# mcu.net
KiCad netlist of a schematic drawn in Altium Designer
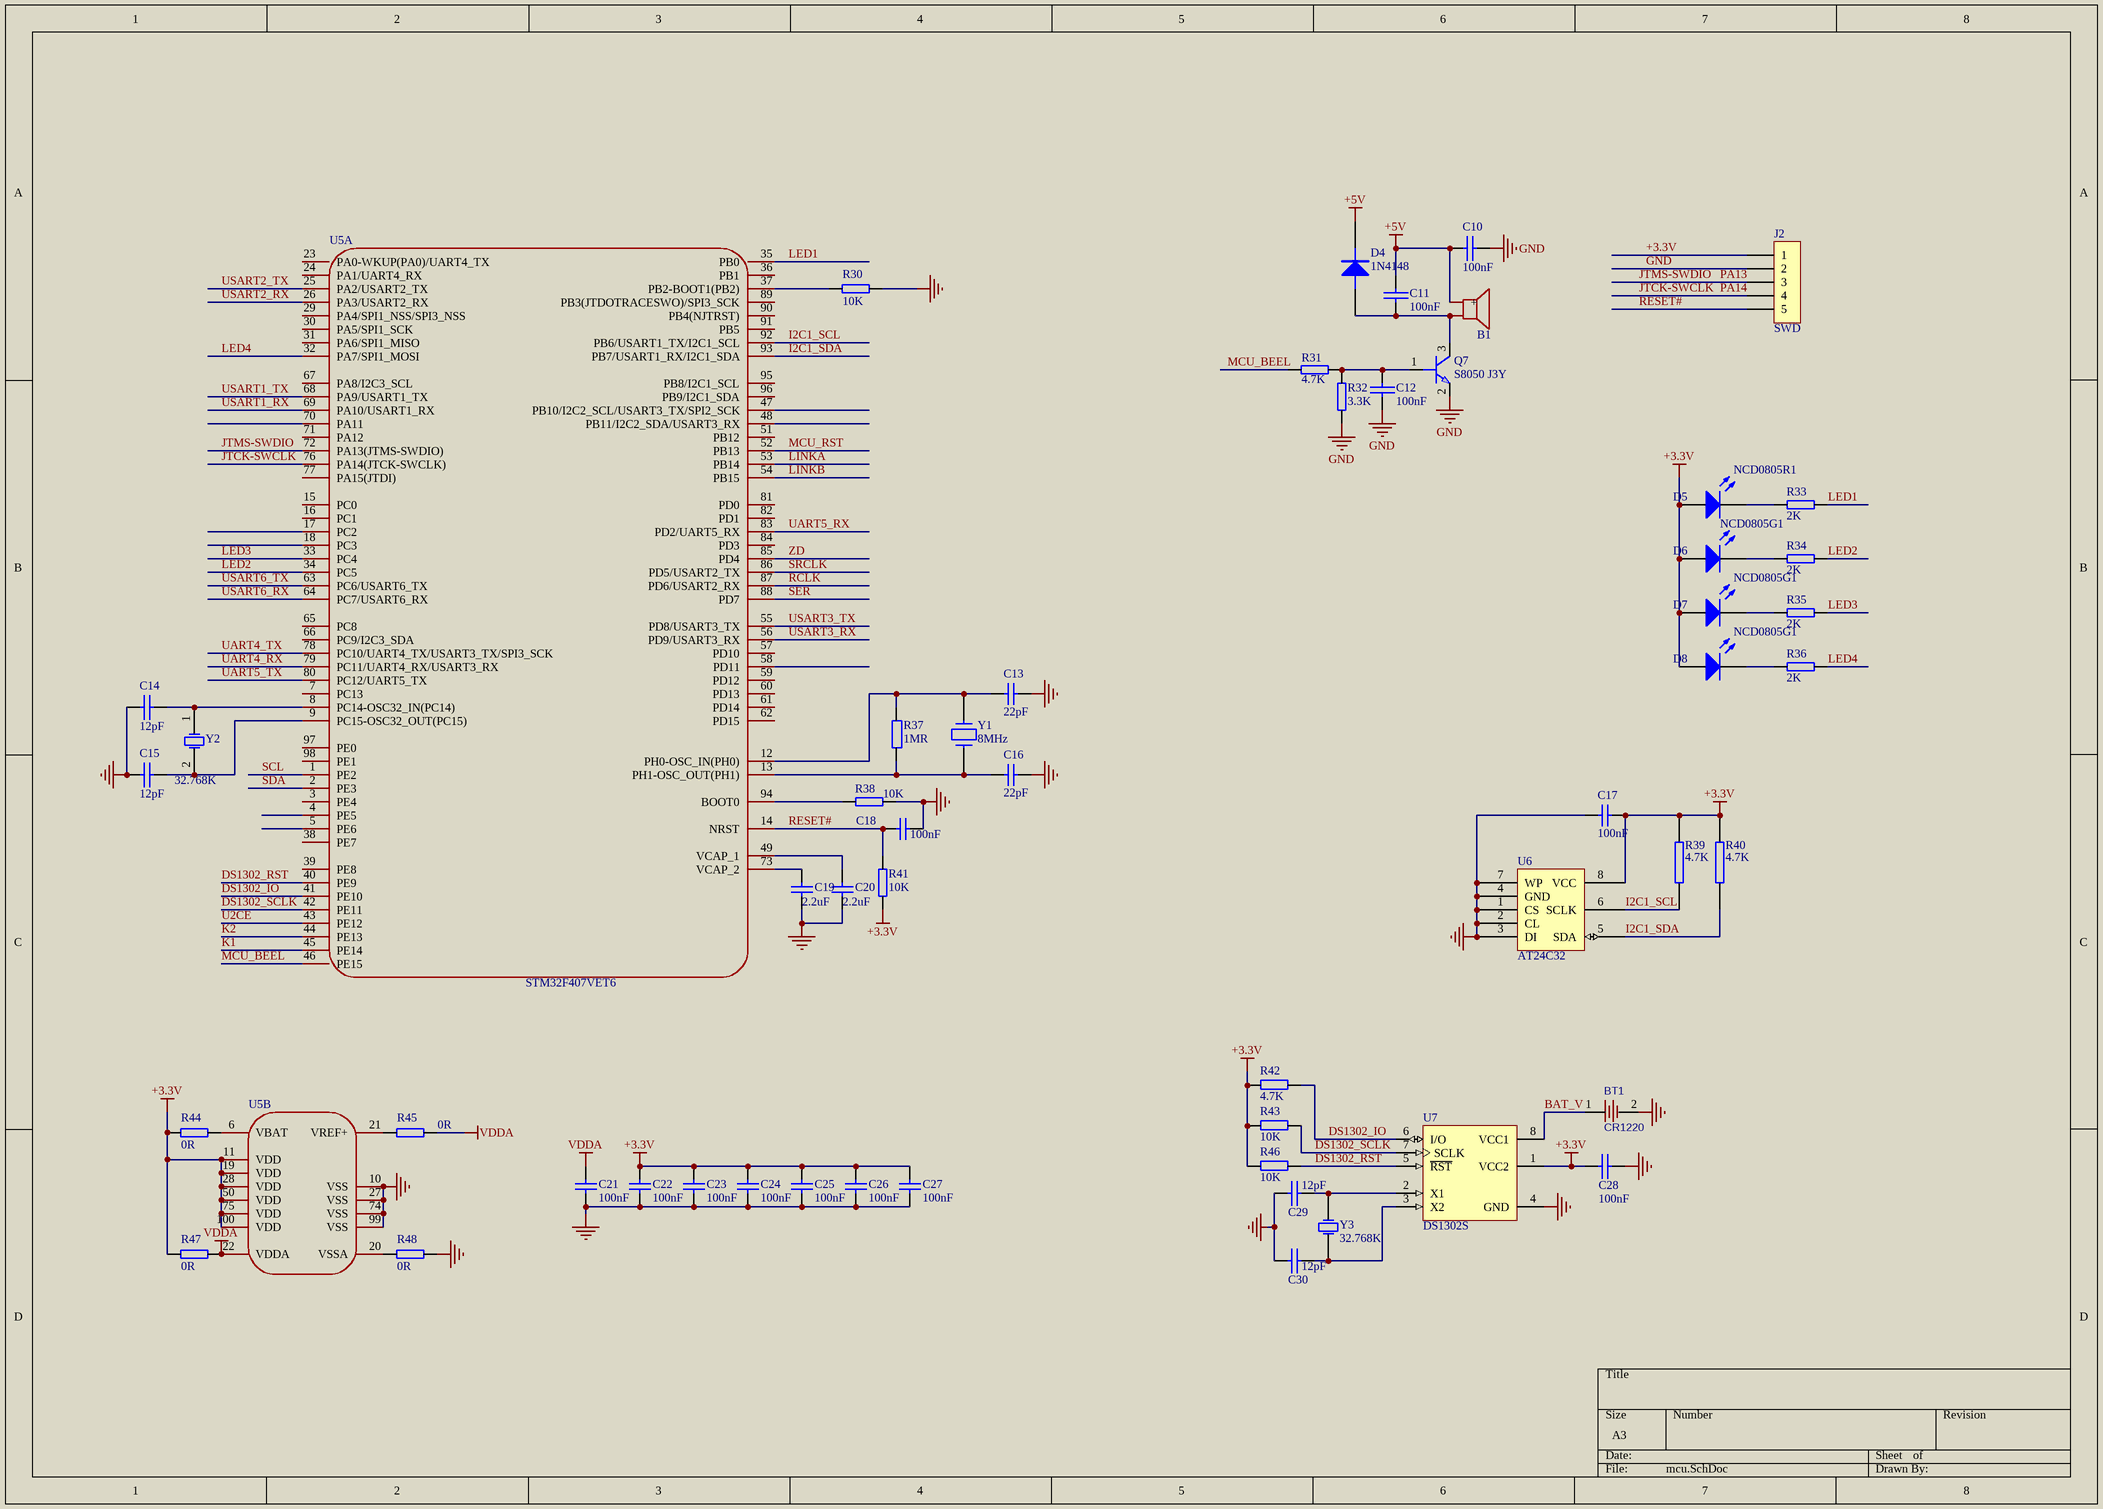
[diagram p0: mcu.SchDoc]

(export (version "E")
  (design (tool "Eeschema 10.0.6"))
  (components
    (comp (ref "B1")
      (value "2.4kHz")
      (footprint "BUZ-TH_BD12.0-P7.60-D0.6-FD")
      (fields (field (name "MANUFACTURER") "华能") (field (name "MANUFACTURER PART") "TMB12A05"))
      (libsource (lib "altium-import") (part "root_0_TMB12A05_C96093_"))
    )
    (comp (ref "BT1")
      (value "CR1220")
      (footprint "BAT-SMD_CR1220-2")
      (fields
        (field (name "BOM_SUPPLIER PART") "C238068")
        (field (name "BOM_MANUFACTURER PART") "1056TR")
        (field (name "CONTRIBUTOR") "LCSC")
      )
      (libsource (lib "altium-import") (part "root_0_1056TR_"))
    )
    (comp (ref "C10")
      (value "100nF")
      (footprint "LC-0805_C")
      (description "Capacitor")
      (libsource (lib "") (part "CAP_1"))
    )
    (comp (ref "C11")
      (value "100nF")
      (footprint "LC-0805_C")
      (description "Capacitor")
      (libsource (lib "") (part "CAP_1"))
    )
    (comp (ref "C12")
      (value "100nF")
      (footprint "LC-0805_C")
      (description "Capacitor")
      (libsource (lib "") (part "CAP_1"))
    )
    (comp (ref "C13")
      (value "22pF")
      (footprint "LC-0805_C")
      (description "Capacitor")
      (fields (field (name "PUBLISHER") "Altium Limited"))
      (libsource (lib "*") (part "CAP"))
    )
    (comp (ref "C14")
      (value "12pF")
      (footprint "LC-0805_C")
      (description "Capacitor")
      (libsource (lib "*") (part "普通电容"))
    )
    (comp (ref "C15")
      (value "12pF")
      (footprint "LC-0805_C")
      (description "Capacitor")
      (libsource (lib "*") (part "普通电容"))
    )
    (comp (ref "C16")
      (value "22pF")
      (footprint "LC-0805_C")
      (description "Capacitor")
      (fields (field (name "PUBLISHER") "Altium Limited"))
      (libsource (lib "*") (part "CAP"))
    )
    (comp (ref "C17")
      (value "100nF")
      (footprint "LC-0805_C")
      (description "Capacitor")
      (fields (field (name "PUBLISHER") "Altium Limited"))
      (libsource (lib "*") (part "CAP"))
    )
    (comp (ref "C18")
      (value "100nF")
      (footprint "LC-0805_C")
      (description "Capacitor")
      (fields (field (name "PUBLISHER") "Altium Limited"))
      (libsource (lib "*") (part "CAP"))
    )
    (comp (ref "C19")
      (value "2.2uF")
      (footprint "LC-0805_C")
      (description "Capacitor")
      (fields (field (name "PUBLISHER") "Altium Limited"))
      (libsource (lib "*") (part "CAP"))
    )
    (comp (ref "C20")
      (value "2.2uF")
      (footprint "LC-0805_C")
      (description "Capacitor")
      (fields (field (name "PUBLISHER") "Altium Limited"))
      (libsource (lib "*") (part "CAP"))
    )
    (comp (ref "C21")
      (value "100nF")
      (footprint "LC-0805_C")
      (description "Capacitor")
      (fields (field (name "PUBLISHER") "Altium Limited"))
      (libsource (lib "*") (part "CAP"))
    )
    (comp (ref "C22")
      (value "100nF")
      (footprint "LC-0805_C")
      (description "Capacitor")
      (fields (field (name "PUBLISHER") "Altium Limited"))
      (libsource (lib "*") (part "CAP"))
    )
    (comp (ref "C23")
      (value "100nF")
      (footprint "LC-0805_C")
      (description "Capacitor")
      (fields (field (name "PUBLISHER") "Altium Limited"))
      (libsource (lib "*") (part "CAP"))
    )
    (comp (ref "C24")
      (value "100nF")
      (footprint "LC-0805_C")
      (description "Capacitor")
      (fields (field (name "PUBLISHER") "Altium Limited"))
      (libsource (lib "*") (part "CAP"))
    )
    (comp (ref "C25")
      (value "100nF")
      (footprint "LC-0805_C")
      (description "Capacitor")
      (fields (field (name "PUBLISHER") "Altium Limited"))
      (libsource (lib "*") (part "CAP"))
    )
    (comp (ref "C26")
      (value "100nF")
      (footprint "LC-0805_C")
      (description "Capacitor")
      (fields (field (name "PUBLISHER") "Altium Limited"))
      (libsource (lib "*") (part "CAP"))
    )
    (comp (ref "C27")
      (value "100nF")
      (footprint "LC-0805_C")
      (description "Capacitor")
      (fields (field (name "PUBLISHER") "Altium Limited"))
      (libsource (lib "*") (part "CAP"))
    )
    (comp (ref "C28")
      (value "100nF")
      (footprint "LC-0805_C")
      (description "Capacitor")
      (libsource (lib "*") (part "普通电容"))
    )
    (comp (ref "C29")
      (value "12pF")
      (footprint "LC-0805_C")
      (description "Capacitor")
      (libsource (lib "*") (part "普通电容"))
    )
    (comp (ref "C30")
      (value "12pF")
      (footprint "LC-0805_C")
      (description "Capacitor")
      (libsource (lib "*") (part "普通电容"))
    )
    (comp (ref "D4")
      (value "1N4148")
      (footprint "LC-SOD-123")
      (description "Diode")
      (libsource (lib "*") (part "DIODE"))
    )
    (comp (ref "D5")
      (value "NCD0805R1")
      (footprint "LC-0805_LED_S1")
      (description "Typical RED, GREEN, YELLOW, AMBER GaAs LED")
      (fields (field (name "PUBLISHER") "Altium Limited"))
      (libsource (lib "Miscellaneous Devices") (part "LED2"))
    )
    (comp (ref "D6")
      (value "NCD0805G1")
      (footprint "LC-0805_LED_S1")
      (description "Typical RED, GREEN, YELLOW, AMBER GaAs LED")
      (fields (field (name "PUBLISHER") "Altium Limited"))
      (libsource (lib "Miscellaneous Devices") (part "LED2"))
    )
    (comp (ref "D7")
      (value "NCD0805G1")
      (footprint "LC-0805_LED_S1")
      (description "Typical RED, GREEN, YELLOW, AMBER GaAs LED")
      (fields (field (name "PUBLISHER") "Altium Limited"))
      (libsource (lib "Miscellaneous Devices") (part "LED2"))
    )
    (comp (ref "D8")
      (value "NCD0805G1")
      (footprint "LC-0805_LED_S1")
      (description "Typical RED, GREEN, YELLOW, AMBER GaAs LED")
      (fields (field (name "PUBLISHER") "Altium Limited"))
      (libsource (lib "Miscellaneous Devices") (part "LED2"))
    )
    (comp (ref "J2")
      (value "SWD")
      (footprint "HDR1X5")
      (description "Connector")
      (libsource (lib "*") (part "CON5"))
    )
    (comp (ref "Q7") (value "S8050 J3Y") (footprint "SOT-23") (libsource (lib "*") (part "2N5551")))
    (comp (ref "R30")
      (value "10K")
      (footprint "LC-0805_R")
      (description "1K")
      (libsource (lib "*") (part "RES22"))
    )
    (comp (ref "R31")
      (value "4.7K")
      (footprint "LC-0805_R")
      (description "1K")
      (libsource (lib "*") (part "RES22"))
    )
    (comp (ref "R32")
      (value "3.3K")
      (footprint "LC-0805_R")
      (description "1K")
      (libsource (lib "*") (part "RES22"))
    )
    (comp (ref "R33")
      (value "2K")
      (footprint "LC-0805_R")
      (description "1K")
      (libsource (lib "*") (part "RES22"))
    )
    (comp (ref "R34")
      (value "2K")
      (footprint "LC-0805_R")
      (description "1K")
      (libsource (lib "*") (part "RES22"))
    )
    (comp (ref "R35")
      (value "2K")
      (footprint "LC-0805_R")
      (description "1K")
      (libsource (lib "*") (part "RES22"))
    )
    (comp (ref "R36")
      (value "2K")
      (footprint "LC-0805_R")
      (description "1K")
      (libsource (lib "*") (part "RES22"))
    )
    (comp (ref "R37") (value "1MR") (footprint "LC-0805_R") (libsource (lib "ATK-SIM900A") (part "R")))
    (comp (ref "R38")
      (value "10K")
      (footprint "LC-0805_R")
      (description "1K")
      (libsource (lib "*") (part "RES22"))
    )
    (comp (ref "R39") (value "4.7K") (footprint "LC-0805_R") (libsource (lib "*") (part "RES2")))
    (comp (ref "R40") (value "4.7K") (footprint "LC-0805_R") (libsource (lib "*") (part "RES2")))
    (comp (ref "R41")
      (value "10K")
      (footprint "LC-0805_R")
      (description "1K")
      (libsource (lib "*") (part "RES22"))
    )
    (comp (ref "R42") (value "4.7K") (footprint "LC-0805_R") (libsource (lib "ATK-SIM900A") (part "R")))
    (comp (ref "R43") (value "10K") (footprint "LC-0805_R") (libsource (lib "ATK-SIM900A") (part "R")))
    (comp (ref "R44")
      (value "0R")
      (footprint "LC-0805_R")
      (description "1K")
      (libsource (lib "*") (part "RES22"))
    )
    (comp (ref "R45")
      (value "0R")
      (footprint "LC-0805_R")
      (description "1K")
      (libsource (lib "*") (part "RES22"))
    )
    (comp (ref "R46") (value "10K") (footprint "LC-0805_R") (libsource (lib "ATK-SIM900A") (part "R")))
    (comp (ref "R47")
      (value "0R")
      (footprint "LC-0805_R")
      (description "1K")
      (libsource (lib "*") (part "RES22"))
    )
    (comp (ref "R48")
      (value "0R")
      (footprint "LC-0805_R")
      (description "1K")
      (libsource (lib "*") (part "RES22"))
    )
    (comp (ref "U5")
      (value "STM32F407VET6")
      (footprint "LC-LQFP-100_14x14x05P")
      (fields (field (name "MANUFACTURER") "ST(意法半导体)"))
      (libsource (lib "stm32f407ve") (part "STM32F407VET6"))
    )
    (comp (ref "U6") (value "AT24C32") (footprint "LC-SOIC-8_150mil") (libsource (lib "*") (part "24C64")))
    (comp (ref "U7")
      (value "DS1302S")
      (footprint "LC-SOIC-8_150mil")
      (description "Trickle Charge Timekeeping Chip")
      (fields (field (name "PUBLISHER") "Altium Limited"))
      (libsource (lib "Dallas Peripheral Real Time Clock") (part "DS1302S"))
    )
    (comp (ref "Y1")
      (value "8MHz")
      (footprint "XTALSO")
      (description "Crystal")
      (libsource (lib "*") (part "CRYSTAL"))
    )
    (comp (ref "Y2")
      (value "32.768K")
      (footprint "LC-SMD-3215_2P FC - 135")
      (description "Crystal Oscillator")
      (fields (field (name "PUBLISHER") "Altium Limited"))
      (libsource (lib "") (part "XTAL_1"))
    )
    (comp (ref "Y3")
      (value "32.768K")
      (footprint "LC-SMD-3215_2P FC - 135")
      (description "Crystal Oscillator")
      (fields (field (name "PUBLISHER") "Altium Limited"))
      (libsource (lib "*") (part "XTAL"))
    )
  )
  (nets
    (net (code "1") (name "+3.3V") (class "Default")
      (node (ref "C17") (pin "1") (pinfunction "1_1") (pintype "passive"))
      (node (ref "C22") (pin "2") (pinfunction "2_2") (pintype "passive"))
      (node (ref "C23") (pin "2") (pinfunction "2_2") (pintype "passive"))
      (node (ref "C24") (pin "2") (pinfunction "2_2") (pintype "passive"))
      (node (ref "C25") (pin "2") (pinfunction "2_2") (pintype "passive"))
      (node (ref "C26") (pin "2") (pinfunction "2_2") (pintype "passive"))
      (node (ref "C27") (pin "2") (pinfunction "2_2") (pintype "passive"))
      (node (ref "C28") (pin "1") (pinfunction "1_1") (pintype "passive"))
      (node (ref "D5") (pin "1") (pinfunction "A_1") (pintype "passive"))
      (node (ref "D6") (pin "1") (pinfunction "A_1") (pintype "passive"))
      (node (ref "D7") (pin "1") (pinfunction "A_1") (pintype "passive"))
      (node (ref "D8") (pin "1") (pinfunction "A_1") (pintype "passive"))
      (node (ref "J2") (pin "1") (pinfunction "1_1") (pintype "passive"))
      (node (ref "R39") (pin "2") (pinfunction "2_2") (pintype "passive"))
      (node (ref "R40") (pin "2") (pinfunction "2_2") (pintype "passive"))
      (node (ref "R41") (pin "1") (pintype "passive"))
      (node (ref "R42") (pin "2") (pintype "passive"))
      (node (ref "R43") (pin "2") (pintype "passive"))
      (node (ref "R44") (pin "1") (pintype "passive"))
      (node (ref "R46") (pin "2") (pintype "passive"))
      (node (ref "R47") (pin "1") (pintype "passive"))
      (node (ref "U5") (pin "100") (pinfunction "VDD_100") (pintype "passive"))
      (node (ref "U5") (pin "11") (pinfunction "VDD_11") (pintype "passive"))
      (node (ref "U5") (pin "19") (pinfunction "VDD_19") (pintype "passive"))
      (node (ref "U5") (pin "28") (pinfunction "VDD_28") (pintype "passive"))
      (node (ref "U5") (pin "50") (pinfunction "VDD_50") (pintype "passive"))
      (node (ref "U5") (pin "75") (pinfunction "VDD_75") (pintype "passive"))
      (node (ref "U6") (pin "8") (pinfunction "VCC_8") (pintype "power_in"))
      (node (ref "U7") (pin "1") (pinfunction "VCC2_1") (pintype "power_in"))
    )
    (net (code "2") (name "+5V") (class "Default")
      (node (ref "B1") (pin "1") (pinfunction "+_1") (pintype "passive"))
      (node (ref "C10") (pin "1") (pinfunction "1_1") (pintype "passive"))
      (node (ref "C11") (pin "1") (pinfunction "1_1") (pintype "passive"))
      (node (ref "D4") (pin "2") (pinfunction "K_2") (pintype "passive"))
    )
    (net (code "3") (name "/BAT_V") (class "Default")
      (node (ref "BT1") (pin "1") (pinfunction "1_1") (pintype "passive"))
      (node (ref "U7") (pin "8") (pinfunction "VCC1_8") (pintype "power_in"))
    )
    (net (code "4") (name "/DS1302_IO") (class "Default")
      (node (ref "R42") (pin "1") (pintype "passive"))
      (node (ref "U5") (pin "41") (pinfunction "PE10_41") (pintype "passive"))
      (node (ref "U7") (pin "6") (pinfunction "I/O_6") (pintype "bidirectional"))
    )
    (net (code "5") (name "/DS1302_RST") (class "Default")
      (node (ref "R46") (pin "1") (pintype "passive"))
      (node (ref "U5") (pin "40") (pinfunction "PE9_40") (pintype "passive"))
      (node (ref "U7") (pin "5") (pinfunction "~{RST}_5") (pintype "input"))
    )
    (net (code "6") (name "/DS1302_SCLK") (class "Default")
      (node (ref "R43") (pin "1") (pintype "passive"))
      (node (ref "U5") (pin "42") (pinfunction "PE11_42") (pintype "passive"))
      (node (ref "U7") (pin "7") (pinfunction "SCLK_7") (pintype "input"))
    )
    (net (code "7") (name "/I2C1_SCL") (class "Default")
      (node (ref "R39") (pin "1") (pinfunction "1_1") (pintype "passive"))
      (node (ref "U5") (pin "92") (pinfunction "PB6/USART1_TX/I2C1_SCL_92") (pintype "passive"))
      (node (ref "U6") (pin "6") (pinfunction "SCLK_6") (pintype "passive"))
    )
    (net (code "8") (name "/I2C1_SDA") (class "Default")
      (node (ref "R40") (pin "1") (pinfunction "1_1") (pintype "passive"))
      (node (ref "U5") (pin "93") (pinfunction "PB7/USART1_RX/I2C1_SDA_93") (pintype "passive"))
      (node (ref "U6") (pin "5") (pinfunction "SDA_5") (pintype "bidirectional"))
    )
    (net (code "9") (name "/JTCK-SWCLK") (class "Default")
      (node (ref "J2") (pin "4") (pinfunction "4_4") (pintype "passive"))
      (node (ref "U5") (pin "76") (pinfunction "PA14(JTCK-SWCLK)_76") (pintype "passive"))
    )
    (net (code "10") (name "/JTMS-SWDIO") (class "Default")
      (node (ref "J2") (pin "3") (pinfunction "3_3") (pintype "passive"))
      (node (ref "U5") (pin "72") (pinfunction "PA13(JTMS-SWDIO)_72") (pintype "passive"))
    )
    (net (code "11") (name "/K1") (class "Default")
      (node (ref "U5") (pin "45") (pinfunction "PE14_45") (pintype "passive"))
    )
    (net (code "12") (name "/K2") (class "Default")
      (node (ref "U5") (pin "44") (pinfunction "PE13_44") (pintype "passive"))
    )
    (net (code "13") (name "/LED1") (class "Default")
      (node (ref "R33") (pin "1") (pintype "passive"))
      (node (ref "U5") (pin "35") (pinfunction "PB0_35") (pintype "passive"))
    )
    (net (code "14") (name "/LED2") (class "Default")
      (node (ref "R34") (pin "1") (pintype "passive"))
      (node (ref "U5") (pin "34") (pinfunction "PC5_34") (pintype "passive"))
    )
    (net (code "15") (name "/LED3") (class "Default")
      (node (ref "R35") (pin "1") (pintype "passive"))
      (node (ref "U5") (pin "33") (pinfunction "PC4_33") (pintype "passive"))
    )
    (net (code "16") (name "/LED4") (class "Default")
      (node (ref "R36") (pin "1") (pintype "passive"))
      (node (ref "U5") (pin "32") (pinfunction "PA7/SPI1_MOSI_32") (pintype "passive"))
    )
    (net (code "17") (name "/LINKA") (class "Default")
      (node (ref "U5") (pin "53") (pinfunction "PB14_53") (pintype "passive"))
    )
    (net (code "18") (name "/LINKB") (class "Default")
      (node (ref "U5") (pin "54") (pinfunction "PB15_54") (pintype "passive"))
    )
    (net (code "19") (name "/MCU_BEEL") (class "Default")
      (node (ref "R31") (pin "1") (pintype "passive"))
      (node (ref "U5") (pin "46") (pinfunction "PE15_46") (pintype "passive"))
    )
    (net (code "20") (name "/MCU_RST") (class "Default")
      (node (ref "U5") (pin "52") (pinfunction "PB13_52") (pintype "passive"))
    )
    (net (code "21") (name "/RCLK") (class "Default")
      (node (ref "U5") (pin "87") (pinfunction "PD6/USART2_RX_87") (pintype "passive"))
    )
    (net (code "22") (name "/RESET#") (class "Default")
      (node (ref "C18") (pin "1") (pinfunction "1_1") (pintype "passive"))
      (node (ref "J2") (pin "5") (pinfunction "5_5") (pintype "passive"))
      (node (ref "R41") (pin "2") (pintype "passive"))
      (node (ref "U5") (pin "14") (pinfunction "NRST_14") (pintype "passive"))
    )
    (net (code "23") (name "/SCL") (class "Default")
      (node (ref "U5") (pin "1") (pinfunction "PE2_1") (pintype "passive"))
    )
    (net (code "24") (name "/SDA") (class "Default")
      (node (ref "U5") (pin "2") (pinfunction "PE3_2") (pintype "passive"))
    )
    (net (code "25") (name "/SER") (class "Default")
      (node (ref "U5") (pin "88") (pinfunction "PD7_88") (pintype "passive"))
    )
    (net (code "26") (name "/SRCLK") (class "Default")
      (node (ref "U5") (pin "86") (pinfunction "PD5/USART2_TX_86") (pintype "passive"))
    )
    (net (code "27") (name "/U2CE") (class "Default")
      (node (ref "U5") (pin "43") (pinfunction "PE12_43") (pintype "passive"))
    )
    (net (code "28") (name "/UART4_RX") (class "Default")
      (node (ref "U5") (pin "79") (pinfunction "PC11/UART4_RX/USART3_RX_79") (pintype "passive"))
    )
    (net (code "29") (name "/UART4_TX") (class "Default")
      (node (ref "U5") (pin "78") (pinfunction "PC10/UART4_TX/USART3_TX/SPI3_SCK_78") (pintype "passive"))
    )
    (net (code "30") (name "/UART5_RX") (class "Default")
      (node (ref "U5") (pin "83") (pinfunction "PD2/UART5_RX_83") (pintype "passive"))
    )
    (net (code "31") (name "/UART5_TX") (class "Default")
      (node (ref "U5") (pin "80") (pinfunction "PC12/UART5_TX_80") (pintype "passive"))
    )
    (net (code "32") (name "/USART1_RX") (class "Default")
      (node (ref "U5") (pin "69") (pinfunction "PA10/USART1_RX_69") (pintype "passive"))
    )
    (net (code "33") (name "/USART1_TX") (class "Default")
      (node (ref "U5") (pin "68") (pinfunction "PA9/USART1_TX_68") (pintype "passive"))
    )
    (net (code "34") (name "/USART2_RX") (class "Default")
      (node (ref "U5") (pin "26") (pinfunction "PA3/USART2_RX_26") (pintype "passive"))
    )
    (net (code "35") (name "/USART2_TX") (class "Default")
      (node (ref "U5") (pin "25") (pinfunction "PA2/USART2_TX_25") (pintype "passive"))
    )
    (net (code "36") (name "/USART3_RX") (class "Default")
      (node (ref "U5") (pin "56") (pinfunction "PD9/USART3_RX_56") (pintype "passive"))
    )
    (net (code "37") (name "/USART3_TX") (class "Default")
      (node (ref "U5") (pin "55") (pinfunction "PD8/USART3_TX_55") (pintype "passive"))
    )
    (net (code "38") (name "/USART6_RX") (class "Default")
      (node (ref "U5") (pin "64") (pinfunction "PC7/USART6_RX_64") (pintype "passive"))
    )
    (net (code "39") (name "/USART6_TX") (class "Default")
      (node (ref "U5") (pin "63") (pinfunction "PC6/USART6_TX_63") (pintype "passive"))
    )
    (net (code "40") (name "/ZD") (class "Default")
      (node (ref "U5") (pin "85") (pinfunction "PD4_85") (pintype "passive"))
    )
    (net (code "41") (name "GND") (class "Default")
      (node (ref "BT1") (pin "2") (pinfunction "2_2") (pintype "passive"))
      (node (ref "C10") (pin "2") (pinfunction "2_2") (pintype "passive"))
      (node (ref "C12") (pin "2") (pinfunction "2_2") (pintype "passive"))
      (node (ref "C13") (pin "1") (pinfunction "1_1") (pintype "passive"))
      (node (ref "C14") (pin "1") (pinfunction "1_1") (pintype "passive"))
      (node (ref "C15") (pin "1") (pinfunction "1_1") (pintype "passive"))
      (node (ref "C16") (pin "2") (pinfunction "2_2") (pintype "passive"))
      (node (ref "C17") (pin "2") (pinfunction "2_2") (pintype "passive"))
      (node (ref "C18") (pin "2") (pinfunction "2_2") (pintype "passive"))
      (node (ref "C19") (pin "1") (pinfunction "1_1") (pintype "passive"))
      (node (ref "C20") (pin "1") (pinfunction "1_1") (pintype "passive"))
      (node (ref "C21") (pin "1") (pinfunction "1_1") (pintype "passive"))
      (node (ref "C22") (pin "1") (pinfunction "1_1") (pintype "passive"))
      (node (ref "C23") (pin "1") (pinfunction "1_1") (pintype "passive"))
      (node (ref "C24") (pin "1") (pinfunction "1_1") (pintype "passive"))
      (node (ref "C25") (pin "1") (pinfunction "1_1") (pintype "passive"))
      (node (ref "C26") (pin "1") (pinfunction "1_1") (pintype "passive"))
      (node (ref "C27") (pin "1") (pinfunction "1_1") (pintype "passive"))
      (node (ref "C28") (pin "2") (pinfunction "2_2") (pintype "passive"))
      (node (ref "C29") (pin "1") (pinfunction "1_1") (pintype "passive"))
      (node (ref "C30") (pin "1") (pinfunction "1_1") (pintype "passive"))
      (node (ref "J2") (pin "2") (pinfunction "2_2") (pintype "passive"))
      (node (ref "Q7") (pin "2") (pinfunction "E_2") (pintype "passive"))
      (node (ref "R30") (pin "2") (pintype "passive"))
      (node (ref "R32") (pin "1") (pintype "passive"))
      (node (ref "R38") (pin "2") (pintype "passive"))
      (node (ref "R48") (pin "2") (pintype "passive"))
      (node (ref "U5") (pin "10") (pinfunction "VSS_10") (pintype "passive"))
      (node (ref "U5") (pin "27") (pinfunction "VSS_27") (pintype "passive"))
      (node (ref "U5") (pin "74") (pinfunction "VSS_74") (pintype "passive"))
      (node (ref "U5") (pin "99") (pinfunction "VSS_99") (pintype "passive"))
      (node (ref "U6") (pin "1") (pinfunction "CS_1") (pintype "passive"))
      (node (ref "U6") (pin "2") (pinfunction "CL_2") (pintype "passive"))
      (node (ref "U6") (pin "3") (pinfunction "DI_3") (pintype "passive"))
      (node (ref "U6") (pin "4") (pinfunction "GND_4") (pintype "power_in"))
      (node (ref "U6") (pin "7") (pinfunction "WP_7") (pintype "passive"))
      (node (ref "U7") (pin "4") (pinfunction "GND_4") (pintype "power_in"))
    )
    (net (code "42") (name "Net-(D4-A)") (class "Default")
      (node (ref "B1") (pin "2") (pinfunction "2_2") (pintype "passive"))
      (node (ref "C11") (pin "2") (pinfunction "2_2") (pintype "passive"))
      (node (ref "D4") (pin "1") (pinfunction "A_1") (pintype "passive"))
      (node (ref "Q7") (pin "3") (pinfunction "C_3") (pintype "passive"))
    )
    (net (code "43") (name "Net-(D5-K)") (class "Default")
      (node (ref "D5") (pin "2") (pinfunction "K_2") (pintype "passive"))
      (node (ref "R33") (pin "2") (pintype "passive"))
    )
    (net (code "44") (name "Net-(D6-K)") (class "Default")
      (node (ref "D6") (pin "2") (pinfunction "K_2") (pintype "passive"))
      (node (ref "R34") (pin "2") (pintype "passive"))
    )
    (net (code "45") (name "Net-(D7-K)") (class "Default")
      (node (ref "D7") (pin "2") (pinfunction "K_2") (pintype "passive"))
      (node (ref "R35") (pin "2") (pintype "passive"))
    )
    (net (code "46") (name "Net-(D8-K)") (class "Default")
      (node (ref "D8") (pin "2") (pinfunction "K_2") (pintype "passive"))
      (node (ref "R36") (pin "2") (pintype "passive"))
    )
    (net (code "47") (name "Net-(Q7-B)") (class "Default")
      (node (ref "C12") (pin "1") (pinfunction "1_1") (pintype "passive"))
      (node (ref "Q7") (pin "1") (pinfunction "B_1") (pintype "passive"))
      (node (ref "R31") (pin "2") (pintype "passive"))
      (node (ref "R32") (pin "2") (pintype "passive"))
    )
    (net (code "48") (name "Net-(U5A-BOOT0)") (class "Default")
      (node (ref "R38") (pin "1") (pintype "passive"))
      (node (ref "U5") (pin "94") (pinfunction "BOOT0_94") (pintype "passive"))
    )
    (net (code "49") (name "Net-(U5A-PB2-BOOT1(PB2))") (class "Default")
      (node (ref "R30") (pin "1") (pintype "passive"))
      (node (ref "U5") (pin "37") (pinfunction "PB2-BOOT1(PB2)_37") (pintype "passive"))
    )
    (net (code "50") (name "Net-(U5A-PC14-OSC32_IN(PC14))") (class "Default")
      (node (ref "C14") (pin "2") (pinfunction "2_2") (pintype "passive"))
      (node (ref "U5") (pin "8") (pinfunction "PC14-OSC32_IN(PC14)_8") (pintype "passive"))
      (node (ref "Y2") (pin "1") (pinfunction "OSC1_1") (pintype "passive"))
    )
    (net (code "51") (name "Net-(U5A-PC15-OSC32_OUT(PC15))") (class "Default")
      (node (ref "C15") (pin "2") (pinfunction "2_2") (pintype "passive"))
      (node (ref "U5") (pin "9") (pinfunction "PC15-OSC32_OUT(PC15)_9") (pintype "passive"))
      (node (ref "Y2") (pin "2") (pinfunction "OSC2_2") (pintype "passive"))
    )
    (net (code "52") (name "Net-(U5A-PH0-OSC_IN(PH0))") (class "Default")
      (node (ref "C13") (pin "2") (pinfunction "2_2") (pintype "passive"))
      (node (ref "R37") (pin "2") (pintype "passive"))
      (node (ref "U5") (pin "12") (pinfunction "PH0-OSC_IN(PH0)_12") (pintype "passive"))
      (node (ref "Y1") (pin "1") (pinfunction "1_1") (pintype "passive"))
    )
    (net (code "53") (name "Net-(U5A-PH1-OSC_OUT(PH1))") (class "Default")
      (node (ref "C16") (pin "1") (pinfunction "1_1") (pintype "passive"))
      (node (ref "R37") (pin "1") (pintype "passive"))
      (node (ref "U5") (pin "13") (pinfunction "PH1-OSC_OUT(PH1)_13") (pintype "passive"))
      (node (ref "Y1") (pin "2") (pinfunction "2_2") (pintype "passive"))
    )
    (net (code "54") (name "Net-(U5A-VCAP_1)") (class "Default")
      (node (ref "C20") (pin "2") (pinfunction "2_2") (pintype "passive"))
      (node (ref "U5") (pin "49") (pinfunction "VCAP_1_49") (pintype "passive"))
    )
    (net (code "55") (name "Net-(U5A-VCAP_2)") (class "Default")
      (node (ref "C19") (pin "2") (pinfunction "2_2") (pintype "passive"))
      (node (ref "U5") (pin "73") (pinfunction "VCAP_2_73") (pintype "passive"))
    )
    (net (code "56") (name "Net-(U5B-VBAT)") (class "Default")
      (node (ref "R44") (pin "2") (pintype "passive"))
      (node (ref "U5") (pin "6") (pinfunction "VBAT_6") (pintype "passive"))
    )
    (net (code "57") (name "Net-(U5B-VREF+)") (class "Default")
      (node (ref "R45") (pin "1") (pintype "passive"))
      (node (ref "U5") (pin "21") (pinfunction "VREF+_21") (pintype "passive"))
    )
    (net (code "58") (name "Net-(U5B-VSSA)") (class "Default")
      (node (ref "R48") (pin "1") (pintype "passive"))
      (node (ref "U5") (pin "20") (pinfunction "VSSA_20") (pintype "passive"))
    )
    (net (code "59") (name "Net-(U7-X1)") (class "Default")
      (node (ref "C29") (pin "2") (pinfunction "2_2") (pintype "passive"))
      (node (ref "U7") (pin "2") (pinfunction "X1_2") (pintype "input"))
      (node (ref "Y3") (pin "2") (pinfunction "OSC2_2") (pintype "passive"))
    )
    (net (code "60") (name "Net-(U7-X2)") (class "Default")
      (node (ref "C30") (pin "2") (pinfunction "2_2") (pintype "passive"))
      (node (ref "U7") (pin "3") (pinfunction "X2_3") (pintype "input"))
      (node (ref "Y3") (pin "1") (pinfunction "OSC1_1") (pintype "passive"))
    )
    (net (code "61") (name "VDDA") (class "Default")
      (node (ref "C21") (pin "2") (pinfunction "2_2") (pintype "passive"))
      (node (ref "R45") (pin "2") (pintype "passive"))
      (node (ref "R47") (pin "2") (pintype "passive"))
      (node (ref "U5") (pin "22") (pinfunction "VDDA_22") (pintype "passive"))
    )
    (net (code "62") (name "unconnected-(U5A-PA0-WKUP(PA0){slash}UART4_TX-Pad23)") (class "Default")
      (node (ref "U5") (pin "23") (pinfunction "PA0-WKUP(PA0)/UART4_TX_23") (pintype "passive"))
    )
    (net (code "63") (name "unconnected-(U5A-PA1{slash}UART4_RX-Pad24)") (class "Default")
      (node (ref "U5") (pin "24") (pinfunction "PA1/UART4_RX_24") (pintype "passive"))
    )
    (net (code "64") (name "unconnected-(U5A-PA4{slash}SPI1_NSS{slash}SPI3_NSS-Pad29)") (class "Default")
      (node (ref "U5") (pin "29") (pinfunction "PA4/SPI1_NSS/SPI3_NSS_29") (pintype "passive"))
    )
    (net (code "65") (name "unconnected-(U5A-PA5{slash}SPI1_SCK-Pad30)") (class "Default")
      (node (ref "U5") (pin "30") (pinfunction "PA5/SPI1_SCK_30") (pintype "passive"))
    )
    (net (code "66") (name "unconnected-(U5A-PA6{slash}SPI1_MISO-Pad31)") (class "Default")
      (node (ref "U5") (pin "31") (pinfunction "PA6/SPI1_MISO_31") (pintype "passive"))
    )
    (net (code "67") (name "unconnected-(U5A-PA8{slash}I2C3_SCL-Pad67)") (class "Default")
      (node (ref "U5") (pin "67") (pinfunction "PA8/I2C3_SCL_67") (pintype "passive"))
    )
    (net (code "68") (name "unconnected-(U5A-PA11-Pad70)") (class "Default")
      (node (ref "U5") (pin "70") (pinfunction "PA11_70") (pintype "passive"))
    )
    (net (code "69") (name "unconnected-(U5A-PA12-Pad71)") (class "Default")
      (node (ref "U5") (pin "71") (pinfunction "PA12_71") (pintype "passive"))
    )
    (net (code "70") (name "unconnected-(U5A-PA15(JTDI)-Pad77)") (class "Default")
      (node (ref "U5") (pin "77") (pinfunction "PA15(JTDI)_77") (pintype "passive"))
    )
    (net (code "71") (name "unconnected-(U5A-PB1-Pad36)") (class "Default")
      (node (ref "U5") (pin "36") (pinfunction "PB1_36") (pintype "passive"))
    )
    (net (code "72") (name "unconnected-(U5A-PB3(JTDOTRACESWO){slash}SPI3_SCK-Pad89)") (class "Default")
      (node (ref "U5") (pin "89") (pinfunction "PB3(JTDOTRACESWO)/SPI3_SCK_89") (pintype "passive"))
    )
    (net (code "73") (name "unconnected-(U5A-PB4(NJTRST)-Pad90)") (class "Default")
      (node (ref "U5") (pin "90") (pinfunction "PB4(NJTRST)_90") (pintype "passive"))
    )
    (net (code "74") (name "unconnected-(U5A-PB5-Pad91)") (class "Default")
      (node (ref "U5") (pin "91") (pinfunction "PB5_91") (pintype "passive"))
    )
    (net (code "75") (name "unconnected-(U5A-PB8{slash}I2C1_SCL-Pad95)") (class "Default")
      (node (ref "U5") (pin "95") (pinfunction "PB8/I2C1_SCL_95") (pintype "passive"))
    )
    (net (code "76") (name "unconnected-(U5A-PB9{slash}I2C1_SDA-Pad96)") (class "Default")
      (node (ref "U5") (pin "96") (pinfunction "PB9/I2C1_SDA_96") (pintype "passive"))
    )
    (net (code "77") (name "unconnected-(U5A-PB10{slash}I2C2_SCL{slash}USART3_TX{slash}SPI2_SCK-Pad47)") (class "Default")
      (node (ref "U5") (pin "47") (pinfunction "PB10/I2C2_SCL/USART3_TX/SPI2_SCK_47") (pintype "passive"))
    )
    (net (code "78") (name "unconnected-(U5A-PB11{slash}I2C2_SDA{slash}USART3_RX-Pad48)") (class "Default")
      (node (ref "U5") (pin "48") (pinfunction "PB11/I2C2_SDA/USART3_RX_48") (pintype "passive"))
    )
    (net (code "79") (name "unconnected-(U5A-PB12-Pad51)") (class "Default")
      (node (ref "U5") (pin "51") (pinfunction "PB12_51") (pintype "passive"))
    )
    (net (code "80") (name "unconnected-(U5A-PC0-Pad15)") (class "Default")
      (node (ref "U5") (pin "15") (pinfunction "PC0_15") (pintype "passive"))
    )
    (net (code "81") (name "unconnected-(U5A-PC1-Pad16)") (class "Default")
      (node (ref "U5") (pin "16") (pinfunction "PC1_16") (pintype "passive"))
    )
    (net (code "82") (name "unconnected-(U5A-PC2-Pad17)") (class "Default")
      (node (ref "U5") (pin "17") (pinfunction "PC2_17") (pintype "passive"))
    )
    (net (code "83") (name "unconnected-(U5A-PC3-Pad18)") (class "Default")
      (node (ref "U5") (pin "18") (pinfunction "PC3_18") (pintype "passive"))
    )
    (net (code "84") (name "unconnected-(U5A-PC8-Pad65)") (class "Default")
      (node (ref "U5") (pin "65") (pinfunction "PC8_65") (pintype "passive"))
    )
    (net (code "85") (name "unconnected-(U5A-PC9{slash}I2C3_SDA-Pad66)") (class "Default")
      (node (ref "U5") (pin "66") (pinfunction "PC9/I2C3_SDA_66") (pintype "passive"))
    )
    (net (code "86") (name "unconnected-(U5A-PC13-Pad7)") (class "Default")
      (node (ref "U5") (pin "7") (pinfunction "PC13_7") (pintype "passive"))
    )
    (net (code "87") (name "unconnected-(U5A-PD0-Pad81)") (class "Default")
      (node (ref "U5") (pin "81") (pinfunction "PD0_81") (pintype "passive"))
    )
    (net (code "88") (name "unconnected-(U5A-PD1-Pad82)") (class "Default")
      (node (ref "U5") (pin "82") (pinfunction "PD1_82") (pintype "passive"))
    )
    (net (code "89") (name "unconnected-(U5A-PD3-Pad84)") (class "Default")
      (node (ref "U5") (pin "84") (pinfunction "PD3_84") (pintype "passive"))
    )
    (net (code "90") (name "unconnected-(U5A-PD10-Pad57)") (class "Default")
      (node (ref "U5") (pin "57") (pinfunction "PD10_57") (pintype "passive"))
    )
    (net (code "91") (name "unconnected-(U5A-PD11-Pad58)") (class "Default")
      (node (ref "U5") (pin "58") (pinfunction "PD11_58") (pintype "passive"))
    )
    (net (code "92") (name "unconnected-(U5A-PD12-Pad59)") (class "Default")
      (node (ref "U5") (pin "59") (pinfunction "PD12_59") (pintype "passive"))
    )
    (net (code "93") (name "unconnected-(U5A-PD13-Pad60)") (class "Default")
      (node (ref "U5") (pin "60") (pinfunction "PD13_60") (pintype "passive"))
    )
    (net (code "94") (name "unconnected-(U5A-PD14-Pad61)") (class "Default")
      (node (ref "U5") (pin "61") (pinfunction "PD14_61") (pintype "passive"))
    )
    (net (code "95") (name "unconnected-(U5A-PD15-Pad62)") (class "Default")
      (node (ref "U5") (pin "62") (pinfunction "PD15_62") (pintype "passive"))
    )
    (net (code "96") (name "unconnected-(U5A-PE0-Pad97)") (class "Default")
      (node (ref "U5") (pin "97") (pinfunction "PE0_97") (pintype "passive"))
    )
    (net (code "97") (name "unconnected-(U5A-PE1-Pad98)") (class "Default")
      (node (ref "U5") (pin "98") (pinfunction "PE1_98") (pintype "passive"))
    )
    (net (code "98") (name "unconnected-(U5A-PE4-Pad3)") (class "Default")
      (node (ref "U5") (pin "3") (pinfunction "PE4_3") (pintype "passive"))
    )
    (net (code "99") (name "unconnected-(U5A-PE5-Pad4)") (class "Default")
      (node (ref "U5") (pin "4") (pinfunction "PE5_4") (pintype "passive"))
    )
    (net (code "100") (name "unconnected-(U5A-PE6-Pad5)") (class "Default")
      (node (ref "U5") (pin "5") (pinfunction "PE6_5") (pintype "passive"))
    )
    (net (code "101") (name "unconnected-(U5A-PE7-Pad38)") (class "Default")
      (node (ref "U5") (pin "38") (pinfunction "PE7_38") (pintype "passive"))
    )
    (net (code "102") (name "unconnected-(U5A-PE8-Pad39)") (class "Default")
      (node (ref "U5") (pin "39") (pinfunction "PE8_39") (pintype "passive"))
    )
    (net (code "103") (name "unconnected-(Y3-GND-Pad0)") (class "Default")
      (node (ref "Y3") (pin "0") (pinfunction "GND_0") (pintype "passive"))
    )
  )
)
